# AMC1411_ADC_1.net
KiCad netlist of a schematic drawn in Altium Designer
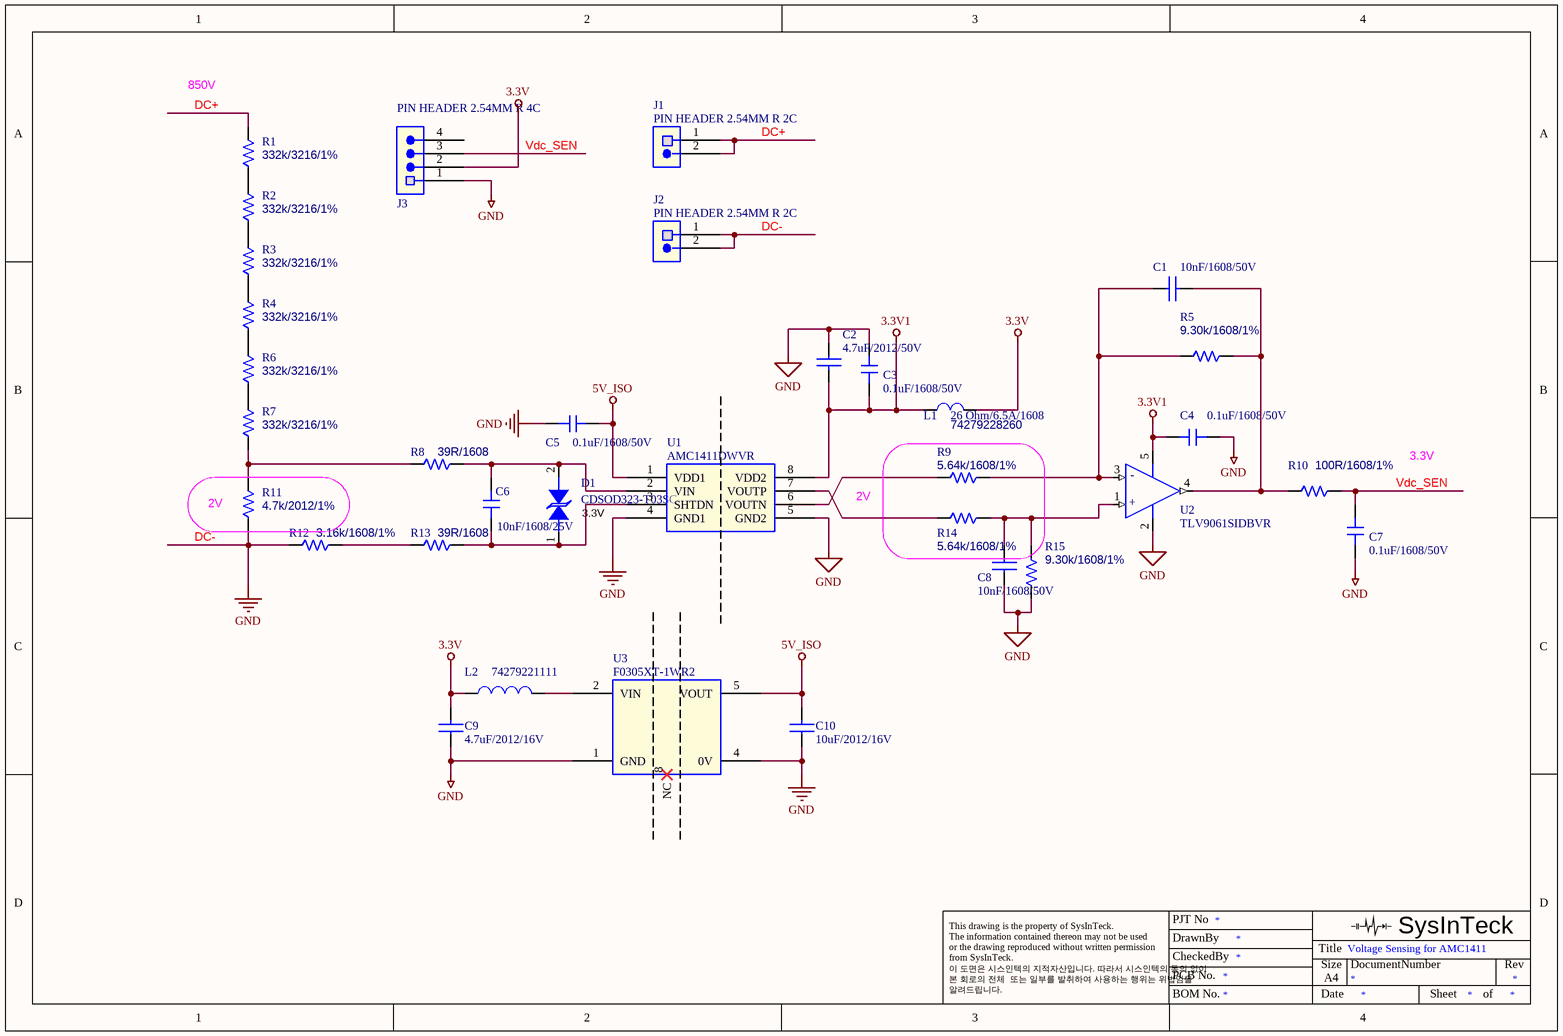
[diagram p0: AMC1411 ADC 센싱회로1.SchDoc]

(export (version "E")
  (design (tool "Eeschema 10.0.6"))
  (components
    (comp (ref "C1")
      (value "10nF/1608/50V")
      (footprint "C-1608")
      (libsource (lib "*") (part "CAPACITOR NON-POL"))
    )
    (comp (ref "C2")
      (value "4.7uF/2012/50V")
      (footprint "C-2012")
      (libsource (lib "*") (part "CAPACITOR NON-POL"))
    )
    (comp (ref "C3")
      (value "0.1uF/1608/50V")
      (footprint "C-1608")
      (libsource (lib "*") (part "CAPACITOR NON-POL_1"))
    )
    (comp (ref "C4")
      (value "0.1uF/1608/50V")
      (footprint "C-1608")
      (libsource (lib "*") (part "CAPACITOR NON-POL_1"))
    )
    (comp (ref "C5")
      (value "0.1uF/1608/50V")
      (footprint "C-1608")
      (libsource (lib "*") (part "CAPACITOR NON-POL_1"))
    )
    (comp (ref "C6")
      (value "10nF/1608/25V")
      (footprint "C-1608")
      (libsource (lib "*") (part "CAPACITOR NON-POL_1"))
    )
    (comp (ref "C7")
      (value "0.1uF/1608/50V")
      (footprint "C-1608")
      (libsource (lib "*") (part "CAPACITOR NON-POL_1"))
    )
    (comp (ref "C8")
      (value "10nF/1608/50V")
      (footprint "C-1608")
      (libsource (lib "*") (part "CAPACITOR NON-POL"))
    )
    (comp (ref "C9")
      (value "4.7uF/2012/16V")
      (footprint "C-2012")
      (libsource (lib "*") (part "CAPACITOR NON-POL"))
    )
    (comp (ref "C10")
      (value "10uF/2012/16V")
      (footprint "C-2012")
      (libsource (lib "*") (part "CAPACITOR NON-POL"))
    )
    (comp (ref "D1")
      (value "CDSOD323-T03SC")
      (footprint "SOD-323")
      (libsource (lib "*") (part "DIODE TVS BI-DIR_0"))
    )
    (comp (ref "J1")
      (value "PIN HEADER 2.54MM R 2C")
      (footprint "PH2.54_1X2PA")
      (libsource (lib "*") (part "CONN TRBLK 2_2"))
    )
    (comp (ref "J2")
      (value "PIN HEADER 2.54MM R 2C")
      (footprint "PH2.54_1X2PA")
      (libsource (lib "*") (part "CONN TRBLK 2_2"))
    )
    (comp (ref "J3")
      (value "PIN HEADER 2.54MM R 4C")
      (footprint "PH2.54_1X4PA")
      (libsource (lib "*") (part "CONN TRBLK 4_2"))
    )
    (comp (ref "L1")
      (value "26 Ohm/6.5A/1608")
      (footprint "L-1608")
      (fields (field (name "PN") "74279228260"))
      (libsource (lib "*") (part "INDUCTOR_2"))
    )
    (comp (ref "L2") (value "74279221111") (footprint "L-3216") (libsource (lib "*") (part "INDUCTOR")))
    (comp (ref "R1") (value "332k/3216/1%") (footprint "R-3216") (libsource (lib "*") (part "R")))
    (comp (ref "R2") (value "332k/3216/1%") (footprint "R-3216") (libsource (lib "*") (part "R")))
    (comp (ref "R3") (value "332k/3216/1%") (footprint "R-3216") (libsource (lib "*") (part "R")))
    (comp (ref "R4") (value "332k/3216/1%") (footprint "R-3216") (libsource (lib "*") (part "R")))
    (comp (ref "R5") (value "9.30k/1608/1%") (footprint "R-1608") (libsource (lib "*") (part "R")))
    (comp (ref "R6") (value "332k/3216/1%") (footprint "R-3216") (libsource (lib "*") (part "R")))
    (comp (ref "R7") (value "332k/3216/1%") (footprint "R-3216") (libsource (lib "*") (part "R")))
    (comp (ref "R8") (value "39R/1608") (footprint "R-1608") (libsource (lib "*") (part "R")))
    (comp (ref "R9") (value "5.64k/1608/1%") (footprint "R-1608") (libsource (lib "*") (part "R")))
    (comp (ref "R10") (value "100R/1608/1%") (footprint "R-1608") (libsource (lib "*") (part "R")))
    (comp (ref "R11") (value "4.7k/2012/1%") (footprint "R-2012") (libsource (lib "*") (part "R")))
    (comp (ref "R12") (value "3.16k/1608/1%") (footprint "R-1608") (libsource (lib "*") (part "R")))
    (comp (ref "R13") (value "39R/1608") (footprint "R-1608") (libsource (lib "*") (part "R")))
    (comp (ref "R14") (value "5.64k/1608/1%") (footprint "R-1608") (libsource (lib "*") (part "R")))
    (comp (ref "R15") (value "9.30k/1608/1%") (footprint "R-1608") (libsource (lib "*") (part "R")))
    (comp (ref "U1")
      (value "AMC1411DWVR")
      (footprint "SO-8-300-400")
      (libsource (lib "*") (part "AMC1311DWVR"))
    )
    (comp (ref "U2")
      (value "TLV9061SIDBVR")
      (footprint "SOT-23-6")
      (libsource (lib "*") (part "TLV1391/SOT_1"))
    )
    (comp (ref "U3")
      (value "F0305XT-1WR2")
      (footprint "DCDC-B_XT-2WR2")
      (libsource (lib "*") (part "F0305XT-1WR2_1"))
    )
  )
  (nets
    (net (code "1") (name "/DC+") (class "Default")
      (node (ref "J1") (pin "1") (pinfunction "1_1") (pintype "passive"))
      (node (ref "J1") (pin "2") (pinfunction "2_2") (pintype "passive"))
      (node (ref "R1") (pin "2") (pinfunction "2_2") (pintype "passive"))
    )
    (net (code "2") (name "/Vdc_SEN") (class "Default")
      (node (ref "C7") (pin "1") (pinfunction "1_1") (pintype "passive"))
      (node (ref "J3") (pin "3") (pinfunction "3_3") (pintype "passive"))
      (node (ref "R10") (pin "1") (pinfunction "1_1") (pintype "passive"))
    )
    (net (code "3") (name "3.3V") (class "Default")
      (node (ref "C9") (pin "2") (pinfunction "2_2") (pintype "passive"))
      (node (ref "J3") (pin "2") (pinfunction "2_2") (pintype "passive"))
      (node (ref "L1") (pin "2") (pinfunction "2_2") (pintype "passive"))
      (node (ref "L2") (pin "1") (pinfunction "1_1") (pintype "passive"))
    )
    (net (code "4") (name "3.3V1") (class "Default")
      (node (ref "C2") (pin "2") (pinfunction "2_2") (pintype "passive"))
      (node (ref "C3") (pin "2") (pinfunction "2_2") (pintype "passive"))
      (node (ref "C4") (pin "1") (pinfunction "1_1") (pintype "passive"))
      (node (ref "L1") (pin "1") (pinfunction "1_1") (pintype "passive"))
      (node (ref "U1") (pin "8") (pinfunction "VDD2_8") (pintype "passive"))
      (node (ref "U2") (pin "5") (pinfunction "V+_5") (pintype "power_in"))
    )
    (net (code "5") (name "5V_ISO") (class "Default")
      (node (ref "C10") (pin "2") (pinfunction "2_2") (pintype "passive"))
      (node (ref "C5") (pin "1") (pinfunction "1_1") (pintype "passive"))
      (node (ref "U1") (pin "1") (pinfunction "VDD1_1") (pintype "passive"))
      (node (ref "U3") (pin "5") (pinfunction "VOUT_5") (pintype "passive"))
    )
    (net (code "6") (name "GND") (class "Default")
      (node (ref "C10") (pin "1") (pinfunction "1_1") (pintype "passive"))
      (node (ref "C2") (pin "1") (pinfunction "1_1") (pintype "passive"))
      (node (ref "C3") (pin "1") (pinfunction "1_1") (pintype "passive"))
      (node (ref "C4") (pin "2") (pinfunction "2_2") (pintype "passive"))
      (node (ref "C5") (pin "2") (pinfunction "2_2") (pintype "passive"))
      (node (ref "C7") (pin "2") (pinfunction "2_2") (pintype "passive"))
      (node (ref "C8") (pin "1") (pinfunction "1_1") (pintype "passive"))
      (node (ref "C9") (pin "1") (pinfunction "1_1") (pintype "passive"))
      (node (ref "J2") (pin "1") (pinfunction "1_1") (pintype "passive"))
      (node (ref "J2") (pin "2") (pinfunction "2_2") (pintype "passive"))
      (node (ref "J3") (pin "1") (pinfunction "1_1") (pintype "passive"))
      (node (ref "R11") (pin "1") (pinfunction "1_1") (pintype "passive"))
      (node (ref "R12") (pin "2") (pinfunction "2_2") (pintype "passive"))
      (node (ref "R15") (pin "2") (pinfunction "2_2") (pintype "passive"))
      (node (ref "U1") (pin "4") (pinfunction "GND1_4") (pintype "passive"))
      (node (ref "U1") (pin "5") (pinfunction "GND2_5") (pintype "passive"))
      (node (ref "U2") (pin "2") (pinfunction "V-_2") (pintype "power_in"))
      (node (ref "U3") (pin "1") (pinfunction "GND_1") (pintype "passive"))
      (node (ref "U3") (pin "4") (pinfunction "0V_4") (pintype "passive"))
    )
    (net (code "7") (name "Net-(R1-Pad1)") (class "Default")
      (node (ref "R1") (pin "1") (pinfunction "1_1") (pintype "passive"))
      (node (ref "R2") (pin "2") (pinfunction "2_2") (pintype "passive"))
    )
    (net (code "8") (name "Net-(R2-Pad1)") (class "Default")
      (node (ref "R2") (pin "1") (pinfunction "1_1") (pintype "passive"))
      (node (ref "R3") (pin "2") (pinfunction "2_2") (pintype "passive"))
    )
    (net (code "9") (name "Net-(R3-Pad1)") (class "Default")
      (node (ref "R3") (pin "1") (pinfunction "1_1") (pintype "passive"))
      (node (ref "R4") (pin "2") (pinfunction "2_2") (pintype "passive"))
    )
    (net (code "10") (name "Net-(R4-Pad1)") (class "Default")
      (node (ref "R4") (pin "1") (pinfunction "1_1") (pintype "passive"))
      (node (ref "R6") (pin "2") (pinfunction "2_2") (pintype "passive"))
    )
    (net (code "11") (name "Net-(R6-Pad1)") (class "Default")
      (node (ref "R6") (pin "1") (pinfunction "1_1") (pintype "passive"))
      (node (ref "R7") (pin "2") (pinfunction "2_2") (pintype "passive"))
    )
    (net (code "12") (name "Net-(R11-Pad2)") (class "Default")
      (node (ref "R11") (pin "2") (pinfunction "2_2") (pintype "passive"))
      (node (ref "R7") (pin "1") (pinfunction "1_1") (pintype "passive"))
      (node (ref "R8") (pin "2") (pinfunction "2_2") (pintype "passive"))
    )
    (net (code "13") (name "Net-(R12-Pad1)") (class "Default")
      (node (ref "R12") (pin "1") (pinfunction "1_1") (pintype "passive"))
      (node (ref "R13") (pin "2") (pinfunction "2_2") (pintype "passive"))
    )
    (net (code "14") (name "Net-(U1-SHTDN)") (class "Default")
      (node (ref "C6") (pin "2") (pinfunction "2_2") (pintype "passive"))
      (node (ref "D1") (pin "1") (pinfunction "1_1") (pintype "passive"))
      (node (ref "R13") (pin "1") (pinfunction "1_1") (pintype "passive"))
      (node (ref "U1") (pin "3") (pinfunction "SHTDN_3") (pintype "passive"))
    )
    (net (code "15") (name "Net-(U1-VIN)") (class "Default")
      (node (ref "C6") (pin "1") (pinfunction "1_1") (pintype "passive"))
      (node (ref "D1") (pin "2") (pinfunction "2_2") (pintype "passive"))
      (node (ref "R8") (pin "1") (pinfunction "1_1") (pintype "passive"))
      (node (ref "U1") (pin "2") (pinfunction "VIN_2") (pintype "passive"))
    )
    (net (code "16") (name "Net-(U1-VOUTN)") (class "Default")
      (node (ref "R9") (pin "2") (pinfunction "2_2") (pintype "passive"))
      (node (ref "U1") (pin "6") (pinfunction "VOUTN_6") (pintype "passive"))
    )
    (net (code "17") (name "Net-(U1-VOUTP)") (class "Default")
      (node (ref "R14") (pin "2") (pinfunction "2_2") (pintype "passive"))
      (node (ref "U1") (pin "7") (pinfunction "VOUTP_7") (pintype "passive"))
    )
    (net (code "18") (name "Net-(U2-+IN)") (class "Default")
      (node (ref "C8") (pin "2") (pinfunction "2_2") (pintype "passive"))
      (node (ref "R14") (pin "1") (pinfunction "1_1") (pintype "passive"))
      (node (ref "R15") (pin "1") (pinfunction "1_1") (pintype "passive"))
      (node (ref "U2") (pin "1") (pinfunction "+IN_1") (pintype "input"))
    )
    (net (code "19") (name "Net-(U2-OUT)") (class "Default")
      (node (ref "C1") (pin "2") (pinfunction "2_2") (pintype "passive"))
      (node (ref "R10") (pin "2") (pinfunction "2_2") (pintype "passive"))
      (node (ref "R5") (pin "1") (pinfunction "1_1") (pintype "passive"))
      (node (ref "U2") (pin "4") (pinfunction "OUT_4") (pintype "output"))
    )
    (net (code "20") (name "Net-(U2-~{-IN})") (class "Default")
      (node (ref "C1") (pin "1") (pinfunction "1_1") (pintype "passive"))
      (node (ref "R5") (pin "2") (pinfunction "2_2") (pintype "passive"))
      (node (ref "R9") (pin "1") (pinfunction "1_1") (pintype "passive"))
      (node (ref "U2") (pin "3") (pinfunction "~{-IN}_3") (pintype "input"))
    )
    (net (code "21") (name "Net-(U3-VIN)") (class "Default")
      (node (ref "L2") (pin "2") (pinfunction "2_2") (pintype "passive"))
      (node (ref "U3") (pin "2") (pinfunction "VIN_2") (pintype "passive"))
    )
    (net (code "22") (name "unconnected-(J3-Pad4)") (class "Default")
      (node (ref "J3") (pin "4") (pinfunction "4_4") (pintype "passive"))
    )
    (net (code "23") (name "unconnected-(U3-NC-Pad8)") (class "Default")
      (node (ref "U3") (pin "8") (pinfunction "NC_8") (pintype "passive+no_connect"))
    )
  )
)
